# ISL6236_DEMO.net
KiCad netlist of a schematic drawn in Altium Designer
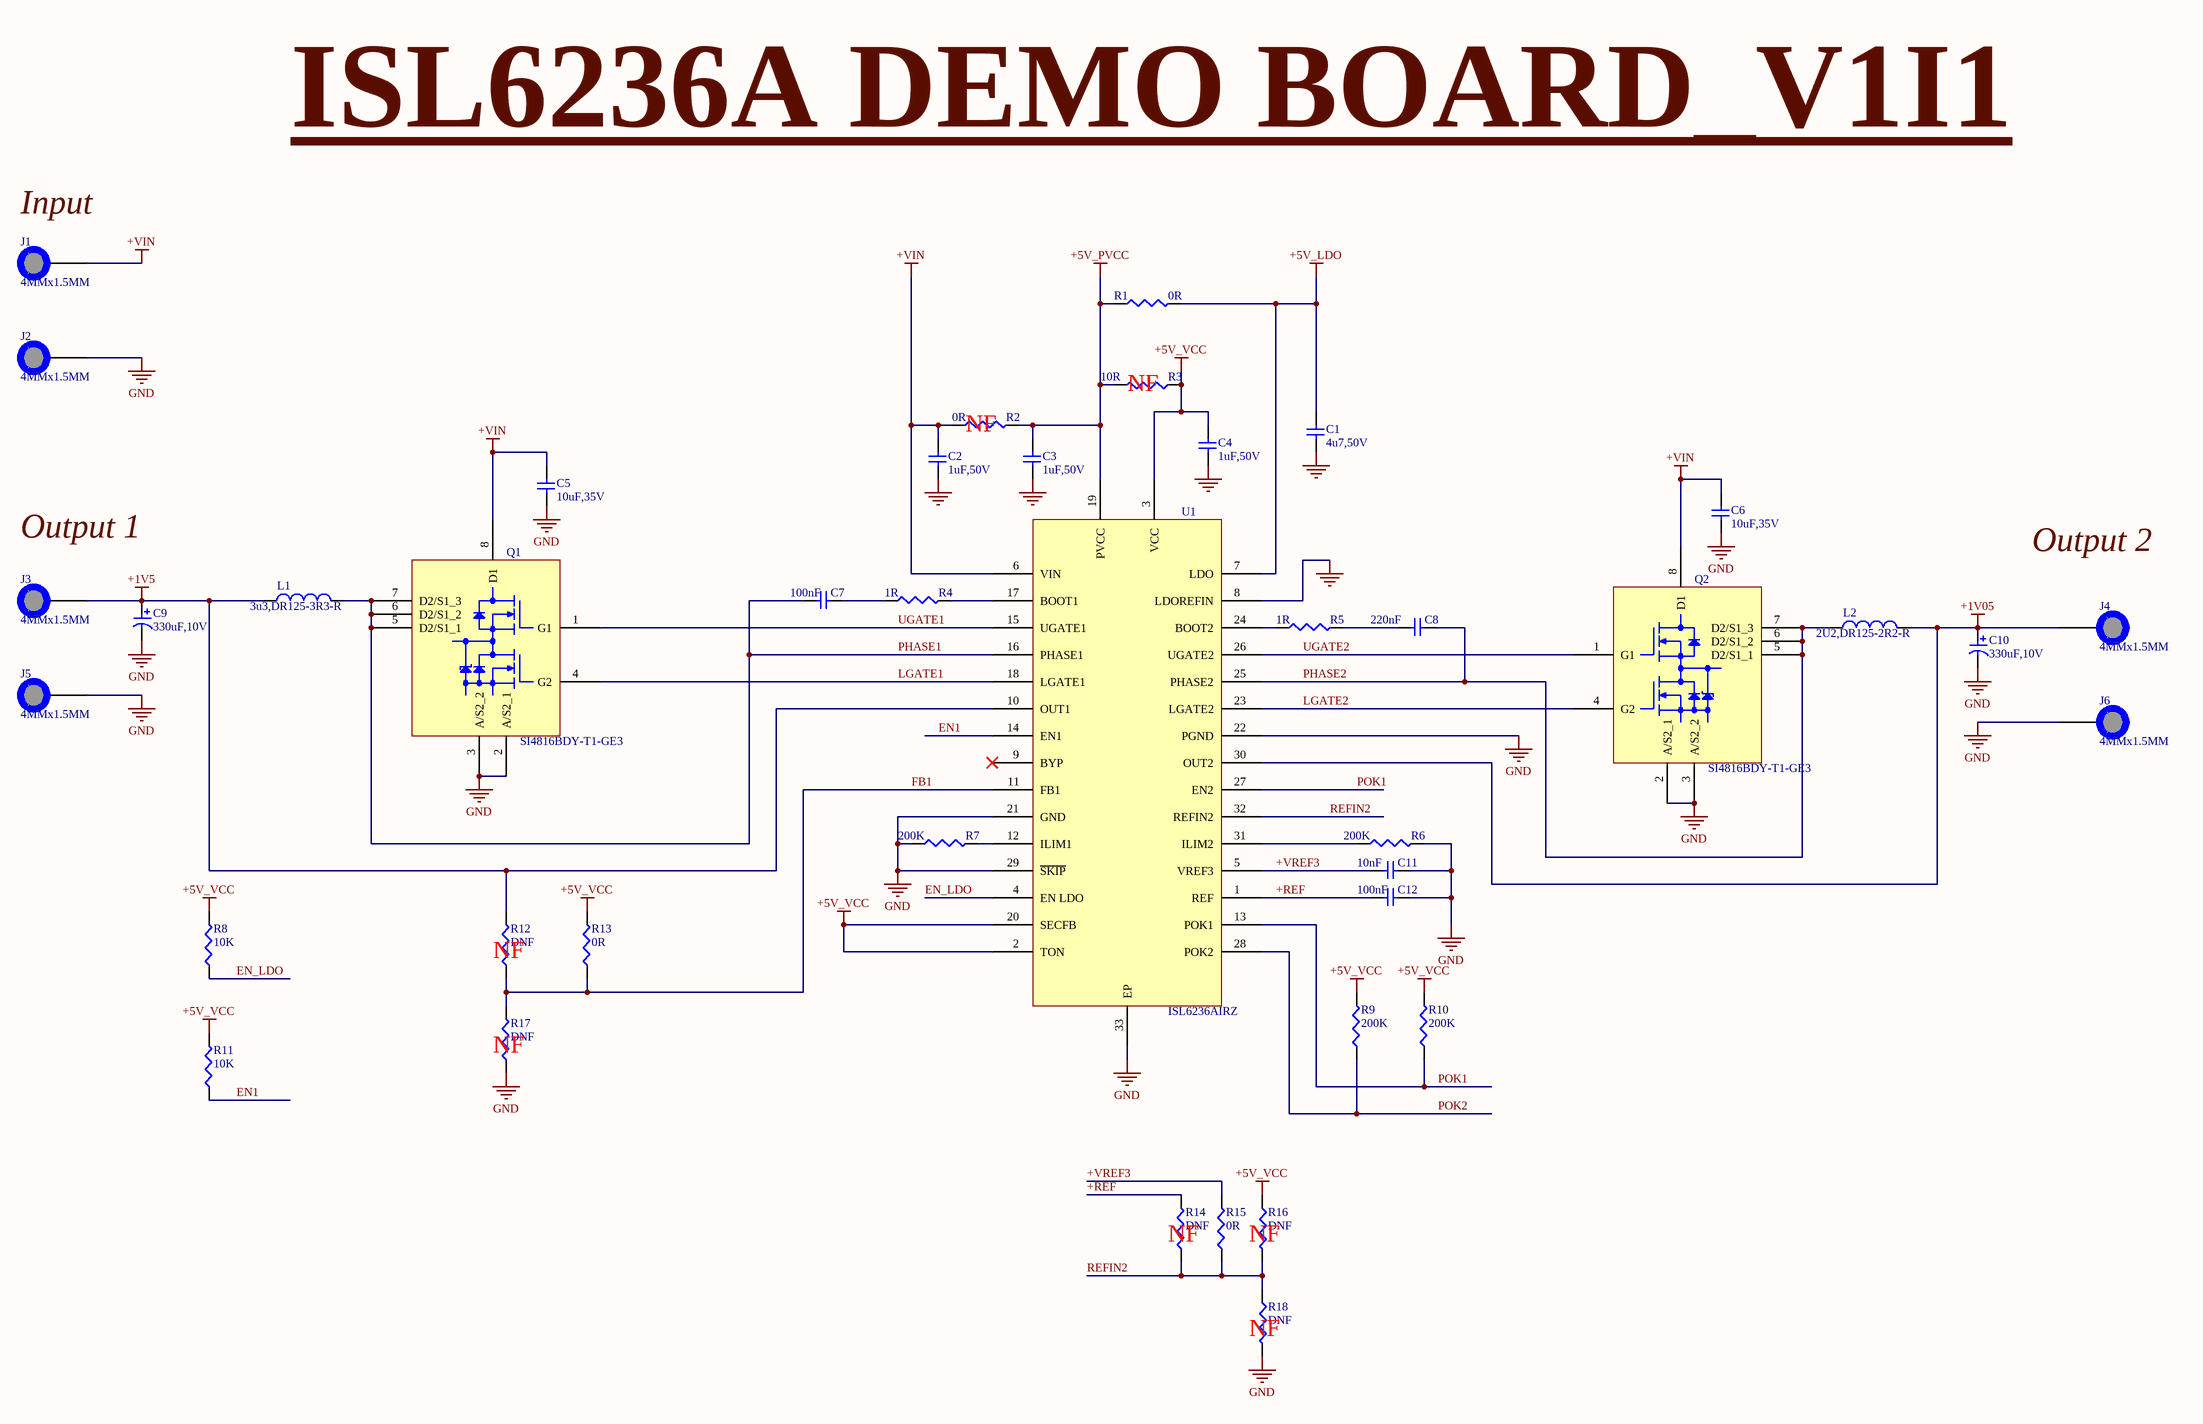
[diagram p0: ISL6236 DEMO.SchDoc]

(export (version "E")
  (design (tool "Eeschema 10.0.6"))
  (components
    (comp (ref "C1")
      (value "4u7,50V")
      (footprint "C1206")
      (description "C Series 1206 4.7 uF 50 V ±10 % Tolerance X5R SMT Multilayer Ceramic Capacitor")
      (fields (field (name "MANUFACTURER") "TDK") (field (name "TOLERANCE") "10%"))
      (libsource (lib "ISL6236 DEMO") (part "C3216X5R1H475K160AB"))
    )
    (comp (ref "C2")
      (value "1uF,50V")
      (footprint "C0805")
      (description "CAP CER 1UF 50V X7R 0805")
      (fields (field (name "MANUFACTURER") "KEMET") (field (name "TOLERANCE") "10%"))
      (libsource (lib "ISL6236 DEMO") (part "C0805C105K5RACTU"))
    )
    (comp (ref "C3")
      (value "1uF,50V")
      (footprint "C0805")
      (description "CAP CER 1UF 50V X7R 0805")
      (fields (field (name "MANUFACTURER") "KEMET") (field (name "TOLERANCE") "10%"))
      (libsource (lib "ISL6236 DEMO") (part "C0805C105K5RACTU"))
    )
    (comp (ref "C4")
      (value "1uF,50V")
      (footprint "C0805")
      (description "CAP CER 1UF 50V X7R 0805")
      (fields (field (name "MANUFACTURER") "KEMET") (field (name "TOLERANCE") "10%"))
      (libsource (lib "ISL6236 DEMO") (part "C0805C105K5RACTU"))
    )
    (comp (ref "C5")
      (value "10uF,35V")
      (footprint "C1210")
      (fields
        (field (name "MANUFACTURER") "KEMET")
        (field (name "VOLTAGE") "35V")
        (field (name "TOLERANCE") "10%")
      )
      (libsource (lib "ISL6236 DEMO") (part "C1210C106K6PACTU"))
    )
    (comp (ref "C6")
      (value "10uF,35V")
      (footprint "C1210")
      (fields
        (field (name "MANUFACTURER") "KEMET")
        (field (name "VOLTAGE") "35V")
        (field (name "TOLERANCE") "10%")
      )
      (libsource (lib "ISL6236 DEMO") (part "C1210C106K6PACTU"))
    )
    (comp (ref "C7")
      (value "100nF")
      (footprint "C0805")
      (description "Cap Ceramic 0.1uF 50V X7R 10% SMD 2.0 x 1.2 mm 125 C Paper T/R")
      (fields (field (name "MANUFACTURER") "KEMET") (field (name "TOLERANCE") "10%"))
      (libsource (lib "ISL6236 DEMO") (part "C0805C104K5RACTU"))
    )
    (comp (ref "C8")
      (value "220nF")
      (footprint "C0805")
      (description "CAP CER 0.22UF 50V X7R 0805")
      (fields (field (name "MANUFACTURER") "KEMET") (field (name "TOLERANCE") "10%"))
      (libsource (lib "ISL6236 DEMO") (part "C0805C224K5RACTU"))
    )
    (comp (ref "C9")
      (value "330uF,10V")
      (footprint "7343-43")
      (description "Tantalum Capacitors - Polymer SMD 330uF 10volts 20%")
      (fields (field (name "MANUFACTURER") "KEMET") (field (name "TOLERANCE") "20%"))
      (libsource (lib "ISL6236 DEMO") (part "T530X337M010ATE004"))
    )
    (comp (ref "C10")
      (value "330uF,10V")
      (footprint "7343-43")
      (description "Tantalum Capacitors - Polymer SMD 330uF 10volts 20%")
      (fields (field (name "MANUFACTURER") "KEMET") (field (name "TOLERANCE") "20%"))
      (libsource (lib "ISL6236 DEMO") (part "T530X337M010ATE004"))
    )
    (comp (ref "C11")
      (value "10nF")
      (footprint "C0805")
      (fields
        (field (name "MANUFACTURER") "KEMET")
        (field (name "TOLERANCE") "10%")
        (field (name "VOLTAGE") "50V")
      )
      (libsource (lib "ISL6236 DEMO") (part "C0805F103K5RACTU"))
    )
    (comp (ref "C12")
      (value "100nF")
      (footprint "C0805")
      (description "Cap Ceramic 0.1uF 50V X7R 10% SMD 2.0 x 1.2 mm 125 C Paper T/R")
      (fields (field (name "MANUFACTURER") "KEMET") (field (name "TOLERANCE") "10%"))
      (libsource (lib "ISL6236 DEMO") (part "C0805C104K5RACTU"))
    )
    (comp (ref "J1")
      (value "4MMx1.5MM")
      (footprint "PAD_WITH_HOLE_4MMx1MM5")
      (description "Pad with a hole 4mm x 1.5mm")
      (libsource (lib "ISL6236 DEMO") (part "PAD_WITH_HOLE_4MMx1MM5"))
    )
    (comp (ref "J2")
      (value "4MMx1.5MM")
      (footprint "PAD_WITH_HOLE_4MMx1MM5")
      (description "Pad with a hole 4mm x 1.5mm")
      (libsource (lib "ISL6236 DEMO") (part "PAD_WITH_HOLE_4MMx1MM5"))
    )
    (comp (ref "J3")
      (value "4MMx1.5MM")
      (footprint "PAD_WITH_HOLE_4MMx1MM5")
      (description "Pad with a hole 4mm x 1.5mm")
      (libsource (lib "ISL6236 DEMO") (part "PAD_WITH_HOLE_4MMx1MM5"))
    )
    (comp (ref "J4")
      (value "4MMx1.5MM")
      (footprint "PAD_WITH_HOLE_4MMx1MM5")
      (description "Pad with a hole 4mm x 1.5mm")
      (libsource (lib "ISL6236 DEMO") (part "PAD_WITH_HOLE_4MMx1MM5"))
    )
    (comp (ref "J5")
      (value "4MMx1.5MM")
      (footprint "PAD_WITH_HOLE_4MMx1MM5")
      (description "Pad with a hole 4mm x 1.5mm")
      (libsource (lib "ISL6236 DEMO") (part "PAD_WITH_HOLE_4MMx1MM5"))
    )
    (comp (ref "J6")
      (value "4MMx1.5MM")
      (footprint "PAD_WITH_HOLE_4MMx1MM5")
      (description "Pad with a hole 4mm x 1.5mm")
      (libsource (lib "ISL6236 DEMO") (part "PAD_WITH_HOLE_4MMx1MM5"))
    )
    (comp (ref "L1")
      (value "3u3,DR125-3R3-R")
      (footprint "DR125")
      (fields
        (field (name "MANUFACTURER") "Eaton Coiltronics")
        (field (name "TOLERANCE") "20%")
        (field (name "MANUFACTURER PART NUMBER") "DR125-3R3-R")
      )
      (libsource (lib "ISL6236 DEMO") (part "DR125-3R3-R"))
    )
    (comp (ref "L2")
      (value "2U2,DR125-2R2-R")
      (footprint "DR125")
      (description "FIXED IND 2.2UH 10.9A 4.5 MOHM")
      (fields (field (name "MANUFACTURER") "Eaton Cooper") (field (name "TOLERANCE") "20%"))
      (libsource (lib "ISL6236 DEMO") (part "DR125-2R2-R"))
    )
    (comp (ref "Q1")
      (value "SI4816BDY-T1-GE3")
      (footprint "SO-8")
      (description "MOSFET 2N-CH 30V 5.8A 8-SOIC")
      (fields (field (name "MANUFACTURER") "Vishay Siliconix"))
      (libsource (lib "") (part "SI4816BDY-T1-GE3_1"))
    )
    (comp (ref "Q2")
      (value "SI4816BDY-T1-GE3")
      (footprint "SO-8")
      (description "MOSFET 2N-CH 30V 5.8A 8-SOIC")
      (fields (field (name "MANUFACTURER") "Vishay Siliconix"))
      (libsource (lib "ISL6236 DEMO") (part "SI4816BDY-T1-GE3"))
    )
    (comp (ref "R1")
      (value "0R")
      (footprint "R0805")
      (description "Thick Film Resistors - SMD 1/8W 0.0ohm 5%")
      (fields (field (name "MANUFACTURER") "Yageo") (field (name "TOLERANCE") "5%"))
      (libsource (lib "ISL6236 DEMO") (part "AC0805JR-070RL"))
    )
    (comp (ref "R2")
      (value "0R")
      (footprint "R0805")
      (description "Thick Film Resistors - SMD 1/8W 0.0ohm 5%")
      (fields (field (name "MANUFACTURER") "Yageo") (field (name "TOLERANCE") "5%"))
      (libsource (lib "ISL6236 DEMO") (part "AC0805JR-070RL"))
    )
    (comp (ref "R3")
      (value "10R")
      (footprint "R0805")
      (fields
        (field (name "MANUFACTURER") "Yageo")
        (field (name "TOLERANCE") "1%")
        (field (name "MANUFACTURER PART NUMBER") "AC0805FR-0710RL")
      )
      (libsource (lib "ISL6236 DEMO") (part "AC0805FR-0710RL"))
    )
    (comp (ref "R4")
      (value "1R")
      (footprint "R0805")
      (description "RES SMD 1 OHM 1% 1/8W 0805")
      (fields (field (name "MANUFACTURER") "Yageo") (field (name "TOLERANCE") "1%"))
      (libsource (lib "ISL6236 DEMO") (part "AC0805FR-071RL"))
    )
    (comp (ref "R5")
      (value "1R")
      (footprint "R0805")
      (description "RES SMD 1 OHM 1% 1/8W 0805")
      (fields (field (name "MANUFACTURER") "Yageo") (field (name "TOLERANCE") "1%"))
      (libsource (lib "ISL6236 DEMO") (part "AC0805FR-071RL"))
    )
    (comp (ref "R6")
      (value "200K")
      (footprint "R0805")
      (description "Res Thick Film 0805 200K Ohm 1% 0.125W(1/8W) ±100ppm/C Epoxy Pad SMD Automotive T/R")
      (fields (field (name "MANUFACTURER") "Yageo") (field (name "TOLERANCE") "1%"))
      (libsource (lib "ISL6236 DEMO") (part "AC0805FR-07200KL"))
    )
    (comp (ref "R7")
      (value "200K")
      (footprint "R0805")
      (description "Res Thick Film 0805 200K Ohm 1% 0.125W(1/8W) ±100ppm/C Epoxy Pad SMD Automotive T/R")
      (fields (field (name "MANUFACTURER") "Yageo") (field (name "TOLERANCE") "1%"))
      (libsource (lib "ISL6236 DEMO") (part "AC0805FR-07200KL"))
    )
    (comp (ref "R8")
      (value "10K")
      (footprint "R0805")
      (description "RES SMD 10K OHM 1% 1/8W 0805")
      (fields (field (name "MANUFACTURER") "Yageo") (field (name "TOLERANCE") "1%"))
      (libsource (lib "ISL6236 DEMO") (part "AC0805FR-0710KL"))
    )
    (comp (ref "R9")
      (value "200K")
      (footprint "R0805")
      (description "Res Thick Film 0805 200K Ohm 1% 0.125W(1/8W) ±100ppm/C Epoxy Pad SMD Automotive T/R")
      (fields (field (name "MANUFACTURER") "Yageo") (field (name "TOLERANCE") "1%"))
      (libsource (lib "ISL6236 DEMO") (part "AC0805FR-07200KL"))
    )
    (comp (ref "R10")
      (value "200K")
      (footprint "R0805")
      (description "Res Thick Film 0805 200K Ohm 1% 0.125W(1/8W) ±100ppm/C Epoxy Pad SMD Automotive T/R")
      (fields (field (name "MANUFACTURER") "Yageo") (field (name "TOLERANCE") "1%"))
      (libsource (lib "ISL6236 DEMO") (part "AC0805FR-07200KL"))
    )
    (comp (ref "R11")
      (value "10K")
      (footprint "R0805")
      (description "RES SMD 10K OHM 1% 1/8W 0805")
      (fields (field (name "MANUFACTURER") "Yageo") (field (name "TOLERANCE") "1%"))
      (libsource (lib "ISL6236 DEMO") (part "AC0805FR-0710KL"))
    )
    (comp (ref "R12") (value "DNF") (footprint "R0805") (libsource (lib "ISL6236 DEMO") (part "RES")))
    (comp (ref "R13")
      (value "0R")
      (footprint "R0805")
      (description "Thick Film Resistors - SMD 1/8W 0.0ohm 5%")
      (fields (field (name "MANUFACTURER") "Yageo") (field (name "TOLERANCE") "5%"))
      (libsource (lib "ISL6236 DEMO") (part "AC0805JR-070RL"))
    )
    (comp (ref "R14") (value "DNF") (footprint "R0805") (libsource (lib "ISL6236 DEMO") (part "RES")))
    (comp (ref "R15")
      (value "0R")
      (footprint "R0805")
      (description "Thick Film Resistors - SMD 1/8W 0.0ohm 5%")
      (fields (field (name "MANUFACTURER") "Yageo") (field (name "TOLERANCE") "5%"))
      (libsource (lib "ISL6236 DEMO") (part "AC0805JR-070RL"))
    )
    (comp (ref "R16") (value "DNF") (footprint "R0805") (libsource (lib "ISL6236 DEMO") (part "RES")))
    (comp (ref "R17") (value "DNF") (footprint "R0805") (libsource (lib "ISL6236 DEMO") (part "RES")))
    (comp (ref "R18") (value "DNF") (footprint "R0805") (libsource (lib "ISL6236 DEMO") (part "RES")))
    (comp (ref "U1")
      (value "ISL6236AIRZ")
      (footprint "L32.5x5B")
      (description "IC MAIN PWR CTRLR QUAD 32-QFN")
      (fields (field (name "MANUFACTURER") "Intersil"))
      (libsource (lib "ISL6236 DEMO") (part "ISL6236AIRZ"))
    )
  )
  (nets
    (net (code "1") (name "+1V05") (class "Default")
      (node (ref "C10") (pin "1") (pinfunction "1_1") (pintype "passive"))
      (node (ref "J4") (pin "1") (pinfunction "1_1") (pintype "passive"))
      (node (ref "L2") (pin "2") (pinfunction "2_2") (pintype "passive"))
      (node (ref "U1") (pin "30") (pinfunction "OUT2_30") (pintype "passive"))
    )
    (net (code "2") (name "+1V5") (class "Default")
      (node (ref "C9") (pin "1") (pinfunction "1_1") (pintype "passive"))
      (node (ref "J3") (pin "1") (pinfunction "1_1") (pintype "passive"))
      (node (ref "L1") (pin "1") (pinfunction "1_1") (pintype "passive"))
      (node (ref "R12") (pin "2") (pinfunction "2_2") (pintype "passive"))
      (node (ref "U1") (pin "10") (pinfunction "OUT1_10") (pintype "passive"))
    )
    (net (code "3") (name "+5V_LDO") (class "Default")
      (node (ref "C1") (pin "2") (pinfunction "2_2") (pintype "passive"))
      (node (ref "R1") (pin "2") (pinfunction "2_2") (pintype "passive"))
      (node (ref "U1") (pin "7") (pinfunction "LDO_7") (pintype "passive"))
    )
    (net (code "4") (name "+5V_PVCC") (class "Default")
      (node (ref "C3") (pin "2") (pinfunction "2_2") (pintype "passive"))
      (node (ref "R1") (pin "1") (pinfunction "1_1") (pintype "passive"))
      (node (ref "R2") (pin "2") (pinfunction "2_2") (pintype "passive"))
      (node (ref "R3") (pin "2") (pinfunction "2_2") (pintype "passive"))
      (node (ref "U1") (pin "19") (pinfunction "PVCC_19") (pintype "passive"))
    )
    (net (code "5") (name "+5V_VCC") (class "Default")
      (node (ref "C4") (pin "2") (pinfunction "2_2") (pintype "passive"))
      (node (ref "R10") (pin "2") (pinfunction "2_2") (pintype "passive"))
      (node (ref "R11") (pin "2") (pinfunction "2_2") (pintype "passive"))
      (node (ref "R13") (pin "2") (pinfunction "2_2") (pintype "passive"))
      (node (ref "R16") (pin "1") (pinfunction "1_1") (pintype "passive"))
      (node (ref "R3") (pin "1") (pinfunction "1_1") (pintype "passive"))
      (node (ref "R8") (pin "2") (pinfunction "2_2") (pintype "passive"))
      (node (ref "R9") (pin "2") (pinfunction "2_2") (pintype "passive"))
      (node (ref "U1") (pin "2") (pinfunction "TON_2") (pintype "passive"))
      (node (ref "U1") (pin "20") (pinfunction "SECFB_20") (pintype "passive"))
      (node (ref "U1") (pin "3") (pinfunction "VCC_3") (pintype "passive"))
    )
    (net (code "6") (name "+VIN") (class "Default")
      (node (ref "C2") (pin "2") (pinfunction "2_2") (pintype "passive"))
      (node (ref "C5") (pin "2") (pinfunction "2_2") (pintype "passive"))
      (node (ref "C6") (pin "2") (pinfunction "2_2") (pintype "passive"))
      (node (ref "J1") (pin "1") (pinfunction "1_1") (pintype "passive"))
      (node (ref "Q1") (pin "8") (pinfunction "D1_8") (pintype "passive"))
      (node (ref "Q2") (pin "8") (pinfunction "D1_8") (pintype "passive"))
      (node (ref "R2") (pin "1") (pinfunction "1_1") (pintype "passive"))
      (node (ref "U1") (pin "6") (pinfunction "VIN_6") (pintype "passive"))
    )
    (net (code "7") (name "/+REF") (class "Default")
      (node (ref "C12") (pin "1") (pinfunction "1_1") (pintype "passive"))
      (node (ref "R14") (pin "2") (pinfunction "2_2") (pintype "passive"))
      (node (ref "U1") (pin "1") (pinfunction "REF_1") (pintype "passive"))
    )
    (net (code "8") (name "/+VREF3") (class "Default")
      (node (ref "C11") (pin "1") (pinfunction "1_1") (pintype "passive"))
      (node (ref "R15") (pin "2") (pinfunction "2_2") (pintype "passive"))
      (node (ref "U1") (pin "5") (pinfunction "VREF3_5") (pintype "passive"))
    )
    (net (code "9") (name "/EN1") (class "Default")
      (node (ref "R11") (pin "1") (pinfunction "1_1") (pintype "passive"))
      (node (ref "U1") (pin "14") (pinfunction "EN1_14") (pintype "passive"))
    )
    (net (code "10") (name "/EN_LDO") (class "Default")
      (node (ref "R8") (pin "1") (pinfunction "1_1") (pintype "passive"))
      (node (ref "U1") (pin "4") (pinfunction "EN_LDO_4") (pintype "passive"))
    )
    (net (code "11") (name "/FB1") (class "Default")
      (node (ref "R12") (pin "1") (pinfunction "1_1") (pintype "passive"))
      (node (ref "R13") (pin "1") (pinfunction "1_1") (pintype "passive"))
      (node (ref "R17") (pin "2") (pinfunction "2_2") (pintype "passive"))
      (node (ref "U1") (pin "11") (pinfunction "FB1_11") (pintype "passive"))
    )
    (net (code "12") (name "/LGATE1") (class "Default")
      (node (ref "Q1") (pin "4") (pinfunction "G2_4") (pintype "passive"))
      (node (ref "U1") (pin "18") (pinfunction "LGATE1_18") (pintype "passive"))
    )
    (net (code "13") (name "/LGATE2") (class "Default")
      (node (ref "Q2") (pin "4") (pinfunction "G2_4") (pintype "passive"))
      (node (ref "U1") (pin "23") (pinfunction "LGATE2_23") (pintype "passive"))
    )
    (net (code "14") (name "/PHASE1") (class "Default")
      (node (ref "C7") (pin "1") (pinfunction "1_1") (pintype "passive"))
      (node (ref "L1") (pin "2") (pinfunction "2_2") (pintype "passive"))
      (node (ref "Q1") (pin "5") (pinfunction "D2/S1_1_5") (pintype "passive"))
      (node (ref "Q1") (pin "6") (pinfunction "D2/S1_2_6") (pintype "passive"))
      (node (ref "Q1") (pin "7") (pinfunction "D2/S1_3_7") (pintype "passive"))
      (node (ref "U1") (pin "16") (pinfunction "PHASE1_16") (pintype "passive"))
    )
    (net (code "15") (name "/PHASE2") (class "Default")
      (node (ref "C8") (pin "2") (pinfunction "2_2") (pintype "passive"))
      (node (ref "L2") (pin "1") (pinfunction "1_1") (pintype "passive"))
      (node (ref "Q2") (pin "5") (pinfunction "D2/S1_1_5") (pintype "passive"))
      (node (ref "Q2") (pin "6") (pinfunction "D2/S1_2_6") (pintype "passive"))
      (node (ref "Q2") (pin "7") (pinfunction "D2/S1_3_7") (pintype "passive"))
      (node (ref "U1") (pin "25") (pinfunction "PHASE2_25") (pintype "passive"))
    )
    (net (code "16") (name "/POK1") (class "Default")
      (node (ref "R10") (pin "1") (pinfunction "1_1") (pintype "passive"))
      (node (ref "U1") (pin "13") (pinfunction "POK1_13") (pintype "passive"))
      (node (ref "U1") (pin "27") (pinfunction "EN2_27") (pintype "passive"))
    )
    (net (code "17") (name "/POK2") (class "Default")
      (node (ref "R9") (pin "1") (pinfunction "1_1") (pintype "passive"))
      (node (ref "U1") (pin "28") (pinfunction "POK2_28") (pintype "passive"))
    )
    (net (code "18") (name "/REFIN2") (class "Default")
      (node (ref "R14") (pin "1") (pinfunction "1_1") (pintype "passive"))
      (node (ref "R15") (pin "1") (pinfunction "1_1") (pintype "passive"))
      (node (ref "R16") (pin "2") (pinfunction "2_2") (pintype "passive"))
      (node (ref "R18") (pin "1") (pinfunction "1_1") (pintype "passive"))
      (node (ref "U1") (pin "32") (pinfunction "REFIN2_32") (pintype "passive"))
    )
    (net (code "19") (name "/UGATE1") (class "Default")
      (node (ref "Q1") (pin "1") (pinfunction "G1_1") (pintype "passive"))
      (node (ref "U1") (pin "15") (pinfunction "UGATE1_15") (pintype "passive"))
    )
    (net (code "20") (name "/UGATE2") (class "Default")
      (node (ref "Q2") (pin "1") (pinfunction "G1_1") (pintype "passive"))
      (node (ref "U1") (pin "26") (pinfunction "UGATE2_26") (pintype "passive"))
    )
    (net (code "21") (name "GND") (class "Default")
      (node (ref "C1") (pin "1") (pinfunction "1_1") (pintype "passive"))
      (node (ref "C10") (pin "2") (pinfunction "2_2") (pintype "passive"))
      (node (ref "C11") (pin "2") (pinfunction "2_2") (pintype "passive"))
      (node (ref "C12") (pin "2") (pinfunction "2_2") (pintype "passive"))
      (node (ref "C2") (pin "1") (pinfunction "1_1") (pintype "passive"))
      (node (ref "C3") (pin "1") (pinfunction "1_1") (pintype "passive"))
      (node (ref "C4") (pin "1") (pinfunction "1_1") (pintype "passive"))
      (node (ref "C5") (pin "1") (pinfunction "1_1") (pintype "passive"))
      (node (ref "C6") (pin "1") (pinfunction "1_1") (pintype "passive"))
      (node (ref "C9") (pin "2") (pinfunction "2_2") (pintype "passive"))
      (node (ref "J2") (pin "1") (pinfunction "1_1") (pintype "passive"))
      (node (ref "J5") (pin "1") (pinfunction "1_1") (pintype "passive"))
      (node (ref "J6") (pin "1") (pinfunction "1_1") (pintype "passive"))
      (node (ref "Q1") (pin "2") (pinfunction "A/S2_1_2") (pintype "passive"))
      (node (ref "Q1") (pin "3") (pinfunction "A/S2_2_3") (pintype "passive"))
      (node (ref "Q2") (pin "2") (pinfunction "A/S2_1_2") (pintype "passive"))
      (node (ref "Q2") (pin "3") (pinfunction "A/S2_2_3") (pintype "passive"))
      (node (ref "R17") (pin "1") (pinfunction "1_1") (pintype "passive"))
      (node (ref "R18") (pin "2") (pinfunction "2_2") (pintype "passive"))
      (node (ref "R6") (pin "2") (pinfunction "2_2") (pintype "passive"))
      (node (ref "R7") (pin "1") (pinfunction "1_1") (pintype "passive"))
      (node (ref "U1") (pin "21") (pinfunction "GND_21") (pintype "passive"))
      (node (ref "U1") (pin "22") (pinfunction "PGND_22") (pintype "passive"))
      (node (ref "U1") (pin "29") (pinfunction "~{SKIP}_29") (pintype "passive"))
      (node (ref "U1") (pin "33") (pinfunction "EP_33") (pintype "passive"))
      (node (ref "U1") (pin "8") (pinfunction "LDOREFIN_8") (pintype "passive"))
    )
    (net (code "22") (name "Net-(C7-Pad2)") (class "Default")
      (node (ref "C7") (pin "2") (pinfunction "2_2") (pintype "passive"))
      (node (ref "R4") (pin "1") (pinfunction "1_1") (pintype "passive"))
    )
    (net (code "23") (name "Net-(C8-Pad1)") (class "Default")
      (node (ref "C8") (pin "1") (pinfunction "1_1") (pintype "passive"))
      (node (ref "R5") (pin "2") (pinfunction "2_2") (pintype "passive"))
    )
    (net (code "24") (name "Net-(U1-BOOT1)") (class "Default")
      (node (ref "R4") (pin "2") (pinfunction "2_2") (pintype "passive"))
      (node (ref "U1") (pin "17") (pinfunction "BOOT1_17") (pintype "passive"))
    )
    (net (code "25") (name "Net-(U1-BOOT2)") (class "Default")
      (node (ref "R5") (pin "1") (pinfunction "1_1") (pintype "passive"))
      (node (ref "U1") (pin "24") (pinfunction "BOOT2_24") (pintype "passive"))
    )
    (net (code "26") (name "Net-(U1-ILIM1)") (class "Default")
      (node (ref "R7") (pin "2") (pinfunction "2_2") (pintype "passive"))
      (node (ref "U1") (pin "12") (pinfunction "ILIM1_12") (pintype "passive"))
    )
    (net (code "27") (name "Net-(U1-ILIM2)") (class "Default")
      (node (ref "R6") (pin "1") (pinfunction "1_1") (pintype "passive"))
      (node (ref "U1") (pin "31") (pinfunction "ILIM2_31") (pintype "passive"))
    )
    (net (code "28") (name "unconnected-(U1-BYP-Pad9)") (class "Default")
      (node (ref "U1") (pin "9") (pinfunction "BYP_9") (pintype "passive+no_connect"))
    )
  )
)
